# MotherBoard_ver2_1.net
KiCad netlist of a schematic drawn in EAGLE
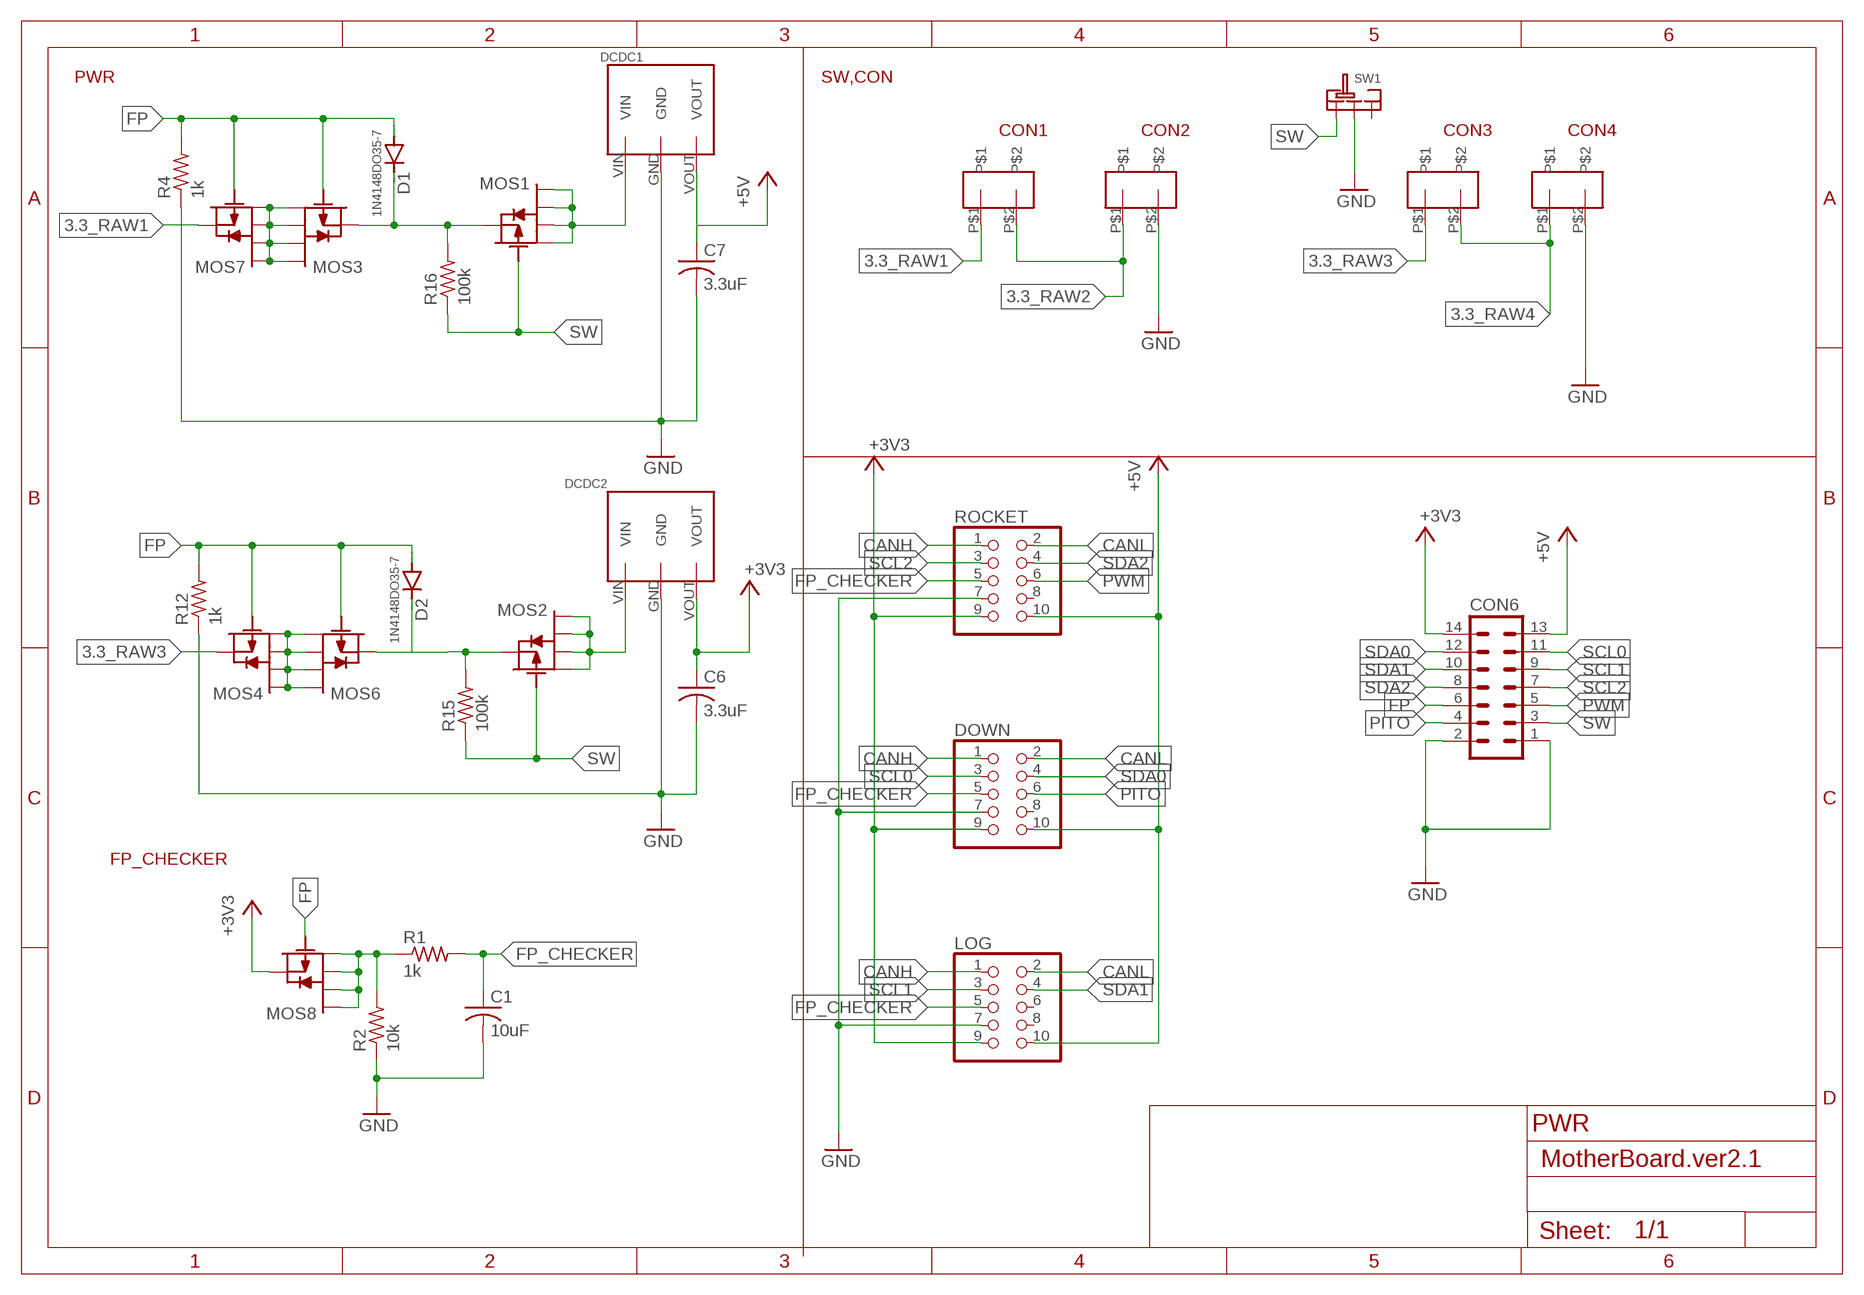
[diagram p0: schematic, sheet 1]

(export (version "E")
  (design (tool "Eeschema 10.0.6"))
  (components
    (comp (ref "C1")
      (value "10uF")
      (footprint "eagle-import:C0603")
      (libsource (lib "eagle-import") (part "C-USC0603"))
    )
    (comp (ref "C6")
      (value "3.3uF")
      (footprint "eagle-import:C0603")
      (libsource (lib "eagle-import") (part "C-USC0603"))
    )
    (comp (ref "C7")
      (value "3.3uF")
      (footprint "eagle-import:C0603")
      (libsource (lib "eagle-import") (part "C-USC0603"))
    )
    (comp (ref "CON1")
      (value "1.25CON2PIN")
      (footprint "eagle-import:1.25CON2PIN")
      (libsource (lib "eagle-import") (part "1.25CON2PIN"))
    )
    (comp (ref "CON2")
      (value "1.25CON2PIN")
      (footprint "eagle-import:1.25CON2PIN")
      (libsource (lib "eagle-import") (part "1.25CON2PIN"))
    )
    (comp (ref "CON3")
      (value "1.25CON2PIN")
      (footprint "eagle-import:1.25CON2PIN")
      (libsource (lib "eagle-import") (part "1.25CON2PIN"))
    )
    (comp (ref "CON4")
      (value "1.25CON2PIN")
      (footprint "eagle-import:1.25CON2PIN")
      (libsource (lib "eagle-import") (part "1.25CON2PIN"))
    )
    (comp (ref "CON6")
      (value "ML14L")
      (footprint "eagle-import:ML14L")
      (libsource (lib "eagle-import") (part "ML14L"))
    )
    (comp (ref "D1")
      (value "1N4148DO35-7")
      (footprint "eagle-import:DO35-7")
      (libsource (lib "eagle-import") (part "1N4148DO35-7"))
    )
    (comp (ref "D2")
      (value "1N4148DO35-7")
      (footprint "eagle-import:DO35-7")
      (libsource (lib "eagle-import") (part "1N4148DO35-7"))
    )
    (comp (ref "DCDC1")
      (value "5V1A_M78AR05-1")
      (footprint "eagle-import:5V1A_M78AR05-1")
      (libsource (lib "eagle-import") (part "5V1A_M78AR05-1"))
    )
    (comp (ref "DCDC2")
      (value "3.3V1A_M78AR033-1")
      (footprint "eagle-import:3.3V1A_M78AR033-1")
      (libsource (lib "eagle-import") (part "3.3V1A_M78AR033-1"))
    )
    (comp (ref "DOWN")
      (value "PINHD-2X5")
      (footprint "eagle-import:2X05")
      (libsource (lib "eagle-import") (part "PINHD-2X5"))
    )
    (comp (ref "LOG")
      (value "PINHD-2X5")
      (footprint "eagle-import:2X05")
      (libsource (lib "eagle-import") (part "PINHD-2X5"))
    )
    (comp (ref "MOS1")
      (value "PCH_SSM6J808R")
      (footprint "eagle-import:SSM6J808R")
      (libsource (lib "eagle-import") (part "PCH_SSM6J808R"))
    )
    (comp (ref "MOS2")
      (value "PCH_SSM6J808R")
      (footprint "eagle-import:SSM6J808R")
      (libsource (lib "eagle-import") (part "PCH_SSM6J808R"))
    )
    (comp (ref "MOS3")
      (value "PCH_SSM6J808R")
      (footprint "eagle-import:SSM6J808R")
      (libsource (lib "eagle-import") (part "PCH_SSM6J808R"))
    )
    (comp (ref "MOS4")
      (value "PCH_SSM6J808R")
      (footprint "eagle-import:SSM6J808R")
      (libsource (lib "eagle-import") (part "PCH_SSM6J808R"))
    )
    (comp (ref "MOS6")
      (value "PCH_SSM6J808R")
      (footprint "eagle-import:SSM6J808R")
      (libsource (lib "eagle-import") (part "PCH_SSM6J808R"))
    )
    (comp (ref "MOS7")
      (value "PCH_SSM6J808R")
      (footprint "eagle-import:SSM6J808R")
      (libsource (lib "eagle-import") (part "PCH_SSM6J808R"))
    )
    (comp (ref "MOS8")
      (value "PCH_SSM6J808R")
      (footprint "eagle-import:SSM6J808R")
      (libsource (lib "eagle-import") (part "PCH_SSM6J808R"))
    )
    (comp (ref "R1")
      (value "1k")
      (footprint "eagle-import:R0603")
      (libsource (lib "eagle-import") (part "R-US_R0603"))
    )
    (comp (ref "R2")
      (value "10k")
      (footprint "eagle-import:R0603")
      (libsource (lib "eagle-import") (part "R-US_R0603"))
    )
    (comp (ref "R4")
      (value "1k")
      (footprint "eagle-import:R0603")
      (libsource (lib "eagle-import") (part "R-US_R0603"))
    )
    (comp (ref "R12")
      (value "1k")
      (footprint "eagle-import:R0603")
      (libsource (lib "eagle-import") (part "R-US_R0603"))
    )
    (comp (ref "R15")
      (value "100k")
      (footprint "eagle-import:R0603")
      (libsource (lib "eagle-import") (part "R-US_R0603"))
    )
    (comp (ref "R16")
      (value "100k")
      (footprint "eagle-import:R0603")
      (libsource (lib "eagle-import") (part "R-US_R0603"))
    )
    (comp (ref "ROCKET")
      (value "PINHD-2X5")
      (footprint "eagle-import:2X05")
      (libsource (lib "eagle-import") (part "PINHD-2X5"))
    )
    (comp (ref "SW1")
      (value "SRIDE_SWITCH")
      (footprint "eagle-import:SRIDE_SWITCH")
      (libsource (lib "eagle-import") (part "SRIDE_SWITCH"))
    )
  )
  (nets
    (net (code "1") (name "+3V3") (class "Default")
      (node (ref "C6") (pin "1") (pinfunction "1_1") (pintype "passive"))
      (node (ref "CON6") (pin "14") (pinfunction "14_14") (pintype "passive"))
      (node (ref "DCDC2") (pin "VOUT") (pinfunction "VOUT_VOUT") (pintype "bidirectional"))
      (node (ref "DOWN") (pin "9") (pinfunction "9_9") (pintype "passive"))
      (node (ref "LOG") (pin "9") (pinfunction "9_9") (pintype "passive"))
      (node (ref "MOS8") (pin "4") (pinfunction "4_4") (pintype "bidirectional"))
      (node (ref "ROCKET") (pin "9") (pinfunction "9_9") (pintype "passive"))
    )
    (net (code "2") (name "+5V") (class "Default")
      (node (ref "C7") (pin "1") (pinfunction "1_1") (pintype "passive"))
      (node (ref "CON6") (pin "13") (pinfunction "13_13") (pintype "passive"))
      (node (ref "DCDC1") (pin "VOUT") (pinfunction "VOUT_VOUT") (pintype "bidirectional"))
      (node (ref "DOWN") (pin "10") (pinfunction "10_10") (pintype "passive"))
      (node (ref "LOG") (pin "10") (pinfunction "10_10") (pintype "passive"))
      (node (ref "ROCKET") (pin "10") (pinfunction "10_10") (pintype "passive"))
    )
    (net (code "3") (name "3.3_RAW1") (class "Default")
      (node (ref "CON1") (pin "P$1") (pinfunction "P$1_P$1") (pintype "bidirectional"))
      (node (ref "MOS7") (pin "4") (pinfunction "4_4") (pintype "bidirectional"))
    )
    (net (code "4") (name "3.3_RAW2") (class "Default")
      (node (ref "CON1") (pin "P$2") (pinfunction "P$2_P$2") (pintype "bidirectional"))
      (node (ref "CON2") (pin "P$1") (pinfunction "P$1_P$1") (pintype "bidirectional"))
    )
    (net (code "5") (name "3.3_RAW3") (class "Default")
      (node (ref "CON3") (pin "P$1") (pinfunction "P$1_P$1") (pintype "bidirectional"))
      (node (ref "MOS4") (pin "4") (pinfunction "4_4") (pintype "bidirectional"))
    )
    (net (code "6") (name "3.3_RAW4") (class "Default")
      (node (ref "CON3") (pin "P$2") (pinfunction "P$2_P$2") (pintype "bidirectional"))
      (node (ref "CON4") (pin "P$1") (pinfunction "P$1_P$1") (pintype "bidirectional"))
    )
    (net (code "7") (name "CANH") (class "Default")
      (node (ref "DOWN") (pin "1") (pinfunction "1_1") (pintype "passive"))
      (node (ref "LOG") (pin "1") (pinfunction "1_1") (pintype "passive"))
      (node (ref "ROCKET") (pin "1") (pinfunction "1_1") (pintype "passive"))
    )
    (net (code "8") (name "CANL") (class "Default")
      (node (ref "DOWN") (pin "2") (pinfunction "2_2") (pintype "passive"))
      (node (ref "LOG") (pin "2") (pinfunction "2_2") (pintype "passive"))
      (node (ref "ROCKET") (pin "2") (pinfunction "2_2") (pintype "passive"))
    )
    (net (code "9") (name "FP") (class "Default")
      (node (ref "CON6") (pin "6") (pinfunction "6_6") (pintype "passive"))
      (node (ref "D1") (pin "A") (pinfunction "A_A") (pintype "passive"))
      (node (ref "D2") (pin "A") (pinfunction "A_A") (pintype "passive"))
      (node (ref "MOS3") (pin "3") (pinfunction "3_3") (pintype "bidirectional"))
      (node (ref "MOS4") (pin "3") (pinfunction "3_3") (pintype "bidirectional"))
      (node (ref "MOS6") (pin "3") (pinfunction "3_3") (pintype "bidirectional"))
      (node (ref "MOS7") (pin "3") (pinfunction "3_3") (pintype "bidirectional"))
      (node (ref "MOS8") (pin "3") (pinfunction "3_3") (pintype "bidirectional"))
      (node (ref "R12") (pin "2") (pinfunction "2_2") (pintype "passive"))
      (node (ref "R4") (pin "2") (pinfunction "2_2") (pintype "passive"))
    )
    (net (code "10") (name "FP_CHECKER") (class "Default")
      (node (ref "C1") (pin "1") (pinfunction "1_1") (pintype "passive"))
      (node (ref "DOWN") (pin "5") (pinfunction "5_5") (pintype "passive"))
      (node (ref "LOG") (pin "5") (pinfunction "5_5") (pintype "passive"))
      (node (ref "R1") (pin "2") (pinfunction "2_2") (pintype "passive"))
      (node (ref "ROCKET") (pin "5") (pinfunction "5_5") (pintype "passive"))
    )
    (net (code "11") (name "GND") (class "Default")
      (node (ref "C1") (pin "2") (pinfunction "2_2") (pintype "passive"))
      (node (ref "C6") (pin "2") (pinfunction "2_2") (pintype "passive"))
      (node (ref "C7") (pin "2") (pinfunction "2_2") (pintype "passive"))
      (node (ref "CON2") (pin "P$2") (pinfunction "P$2_P$2") (pintype "bidirectional"))
      (node (ref "CON4") (pin "P$2") (pinfunction "P$2_P$2") (pintype "bidirectional"))
      (node (ref "CON6") (pin "1") (pinfunction "1_1") (pintype "passive"))
      (node (ref "CON6") (pin "2") (pinfunction "2_2") (pintype "passive"))
      (node (ref "DCDC1") (pin "GND") (pinfunction "GND_GND") (pintype "bidirectional"))
      (node (ref "DCDC2") (pin "GND") (pinfunction "GND_GND") (pintype "bidirectional"))
      (node (ref "DOWN") (pin "7") (pinfunction "7_7") (pintype "passive"))
      (node (ref "LOG") (pin "7") (pinfunction "7_7") (pintype "passive"))
      (node (ref "R12") (pin "1") (pinfunction "1_1") (pintype "passive"))
      (node (ref "R2") (pin "1") (pinfunction "1_1") (pintype "passive"))
      (node (ref "R4") (pin "1") (pinfunction "1_1") (pintype "passive"))
      (node (ref "ROCKET") (pin "7") (pinfunction "7_7") (pintype "passive"))
      (node (ref "SW1") (pin "LR") (pinfunction "LR_LR") (pintype "bidirectional"))
    )
    (net (code "12") (name "Net-(D1-PadC)") (class "Default")
      (node (ref "D1") (pin "C") (pinfunction "C_C") (pintype "passive"))
      (node (ref "MOS1") (pin "4") (pinfunction "4_4") (pintype "bidirectional"))
      (node (ref "MOS3") (pin "4") (pinfunction "4_4") (pintype "bidirectional"))
      (node (ref "R16") (pin "2") (pinfunction "2_2") (pintype "passive"))
    )
    (net (code "13") (name "Net-(D2-PadC)") (class "Default")
      (node (ref "D2") (pin "C") (pinfunction "C_C") (pintype "passive"))
      (node (ref "MOS2") (pin "4") (pinfunction "4_4") (pintype "bidirectional"))
      (node (ref "MOS6") (pin "4") (pinfunction "4_4") (pintype "bidirectional"))
      (node (ref "R15") (pin "2") (pinfunction "2_2") (pintype "passive"))
    )
    (net (code "14") (name "Net-(DCDC1-PadVIN)") (class "Default")
      (node (ref "DCDC1") (pin "VIN") (pinfunction "VIN_VIN") (pintype "bidirectional"))
      (node (ref "MOS1") (pin "1") (pinfunction "1_1") (pintype "bidirectional"))
      (node (ref "MOS1") (pin "2") (pinfunction "2_2") (pintype "bidirectional"))
      (node (ref "MOS1") (pin "5") (pinfunction "5_5") (pintype "bidirectional"))
      (node (ref "MOS1") (pin "6") (pinfunction "6_6") (pintype "bidirectional"))
    )
    (net (code "15") (name "Net-(DCDC2-PadVIN)") (class "Default")
      (node (ref "DCDC2") (pin "VIN") (pinfunction "VIN_VIN") (pintype "bidirectional"))
      (node (ref "MOS2") (pin "1") (pinfunction "1_1") (pintype "bidirectional"))
      (node (ref "MOS2") (pin "2") (pinfunction "2_2") (pintype "bidirectional"))
      (node (ref "MOS2") (pin "5") (pinfunction "5_5") (pintype "bidirectional"))
      (node (ref "MOS2") (pin "6") (pinfunction "6_6") (pintype "bidirectional"))
    )
    (net (code "16") (name "Net-(MOS3-Pad1)") (class "Default")
      (node (ref "MOS3") (pin "1") (pinfunction "1_1") (pintype "bidirectional"))
      (node (ref "MOS3") (pin "2") (pinfunction "2_2") (pintype "bidirectional"))
      (node (ref "MOS3") (pin "5") (pinfunction "5_5") (pintype "bidirectional"))
      (node (ref "MOS3") (pin "6") (pinfunction "6_6") (pintype "bidirectional"))
      (node (ref "MOS7") (pin "1") (pinfunction "1_1") (pintype "bidirectional"))
      (node (ref "MOS7") (pin "2") (pinfunction "2_2") (pintype "bidirectional"))
      (node (ref "MOS7") (pin "5") (pinfunction "5_5") (pintype "bidirectional"))
      (node (ref "MOS7") (pin "6") (pinfunction "6_6") (pintype "bidirectional"))
    )
    (net (code "17") (name "Net-(MOS4-Pad1)") (class "Default")
      (node (ref "MOS4") (pin "1") (pinfunction "1_1") (pintype "bidirectional"))
      (node (ref "MOS4") (pin "2") (pinfunction "2_2") (pintype "bidirectional"))
      (node (ref "MOS4") (pin "5") (pinfunction "5_5") (pintype "bidirectional"))
      (node (ref "MOS4") (pin "6") (pinfunction "6_6") (pintype "bidirectional"))
      (node (ref "MOS6") (pin "1") (pinfunction "1_1") (pintype "bidirectional"))
      (node (ref "MOS6") (pin "2") (pinfunction "2_2") (pintype "bidirectional"))
      (node (ref "MOS6") (pin "5") (pinfunction "5_5") (pintype "bidirectional"))
      (node (ref "MOS6") (pin "6") (pinfunction "6_6") (pintype "bidirectional"))
    )
    (net (code "18") (name "Net-(MOS8-Pad1)") (class "Default")
      (node (ref "MOS8") (pin "1") (pinfunction "1_1") (pintype "bidirectional"))
      (node (ref "MOS8") (pin "2") (pinfunction "2_2") (pintype "bidirectional"))
      (node (ref "MOS8") (pin "5") (pinfunction "5_5") (pintype "bidirectional"))
      (node (ref "MOS8") (pin "6") (pinfunction "6_6") (pintype "bidirectional"))
      (node (ref "R1") (pin "1") (pinfunction "1_1") (pintype "passive"))
      (node (ref "R2") (pin "2") (pinfunction "2_2") (pintype "passive"))
    )
    (net (code "19") (name "PITO") (class "Default")
      (node (ref "CON6") (pin "4") (pinfunction "4_4") (pintype "passive"))
      (node (ref "DOWN") (pin "6") (pinfunction "6_6") (pintype "passive"))
    )
    (net (code "20") (name "PWM") (class "Default")
      (node (ref "CON6") (pin "5") (pinfunction "5_5") (pintype "passive"))
      (node (ref "ROCKET") (pin "6") (pinfunction "6_6") (pintype "passive"))
    )
    (net (code "21") (name "SCL0") (class "Default")
      (node (ref "CON6") (pin "11") (pinfunction "11_11") (pintype "passive"))
      (node (ref "DOWN") (pin "3") (pinfunction "3_3") (pintype "passive"))
    )
    (net (code "22") (name "SCL1") (class "Default")
      (node (ref "CON6") (pin "9") (pinfunction "9_9") (pintype "passive"))
      (node (ref "LOG") (pin "3") (pinfunction "3_3") (pintype "passive"))
    )
    (net (code "23") (name "SCL2") (class "Default")
      (node (ref "CON6") (pin "7") (pinfunction "7_7") (pintype "passive"))
      (node (ref "ROCKET") (pin "3") (pinfunction "3_3") (pintype "passive"))
    )
    (net (code "24") (name "SDA0") (class "Default")
      (node (ref "CON6") (pin "12") (pinfunction "12_12") (pintype "passive"))
      (node (ref "DOWN") (pin "4") (pinfunction "4_4") (pintype "passive"))
    )
    (net (code "25") (name "SDA1") (class "Default")
      (node (ref "CON6") (pin "10") (pinfunction "10_10") (pintype "passive"))
      (node (ref "LOG") (pin "4") (pinfunction "4_4") (pintype "passive"))
    )
    (net (code "26") (name "SDA2") (class "Default")
      (node (ref "CON6") (pin "8") (pinfunction "8_8") (pintype "passive"))
      (node (ref "ROCKET") (pin "4") (pinfunction "4_4") (pintype "passive"))
    )
    (net (code "27") (name "SW") (class "Default")
      (node (ref "CON6") (pin "3") (pinfunction "3_3") (pintype "passive"))
      (node (ref "MOS1") (pin "3") (pinfunction "3_3") (pintype "bidirectional"))
      (node (ref "MOS2") (pin "3") (pinfunction "3_3") (pintype "bidirectional"))
      (node (ref "R15") (pin "1") (pinfunction "1_1") (pintype "passive"))
      (node (ref "R16") (pin "1") (pinfunction "1_1") (pintype "passive"))
      (node (ref "SW1") (pin "L") (pinfunction "L_L") (pintype "bidirectional"))
    )
    (net (code "28") (name "unconnected-(DOWN-Pad8)") (class "Default")
      (node (ref "DOWN") (pin "8") (pinfunction "8_8") (pintype "passive"))
    )
    (net (code "29") (name "unconnected-(LOG-Pad6)") (class "Default")
      (node (ref "LOG") (pin "6") (pinfunction "6_6") (pintype "passive"))
    )
    (net (code "30") (name "unconnected-(LOG-Pad8)") (class "Default")
      (node (ref "LOG") (pin "8") (pinfunction "8_8") (pintype "passive"))
    )
    (net (code "31") (name "unconnected-(ROCKET-Pad8)") (class "Default")
      (node (ref "ROCKET") (pin "8") (pinfunction "8_8") (pintype "passive"))
    )
    (net (code "32") (name "unconnected-(SW1-PadR)") (class "Default")
      (node (ref "SW1") (pin "R") (pinfunction "R_R") (pintype "bidirectional"))
    )
  )
)
